# Sheet1.net
KiCad netlist of a schematic drawn in Altium Designer
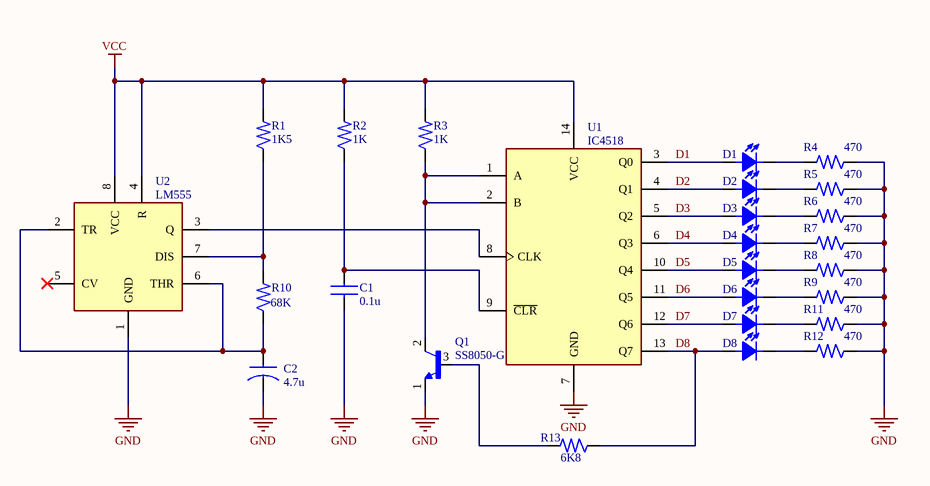
[diagram p0: Sheet1.SchDoc]

(export (version "E")
  (design (tool "Eeschema 10.0.6"))
  (components
    (comp (ref "C1") (value "0.1u") (footprint "CAP_8x11mm") (libsource (lib "Schlib1") (part "CAPACITOR")))
    (comp (ref "C2") (value "4.7u") (footprint "CAP_8x11mm") (libsource (lib "Schlib1") (part "CAPACITOR_1")))
    (comp (ref "D1") (value "LED") (footprint "LED-TH-2.54mm-RED") (libsource (lib "Schlib1") (part "LED")))
    (comp (ref "D2") (value "LED") (footprint "LED-TH-2.54mm-RED") (libsource (lib "Schlib1") (part "LED")))
    (comp (ref "D3") (value "LED") (footprint "LED-TH-2.54mm-RED") (libsource (lib "Schlib1") (part "LED")))
    (comp (ref "D4") (value "LED") (footprint "LED-TH-2.54mm-RED") (libsource (lib "Schlib1") (part "LED")))
    (comp (ref "D5") (value "LED") (footprint "LED-TH-2.54mm-RED") (libsource (lib "Schlib1") (part "LED")))
    (comp (ref "D6") (value "LED") (footprint "LED-TH-2.54mm-RED") (libsource (lib "Schlib1") (part "LED")))
    (comp (ref "D7") (value "LED") (footprint "LED-TH-2.54mm-RED") (libsource (lib "Schlib1") (part "LED")))
    (comp (ref "D8") (value "LED") (footprint "LED-TH-2.54mm-RED") (libsource (lib "Schlib1") (part "LED")))
    (comp (ref "Q1")
      (value "SS8050-G")
      (footprint "TO-92")
      (description "Bipolar (BJT) Transistor NPN 25 V 1.5 A 100MHz 300 mW Surface Mount SOT-23-3")
      (fields (field (name "DIGI-KEY_PART_NUMBER") "641-1790-2-ND") (field (name "MP") "SS8050G"))
      (libsource (lib "Schlib1") (part "SS8050-G"))
    )
    (comp (ref "R1") (value "1K5") (footprint "RES0805_SMD") (libsource (lib "Schlib1") (part "RESISTOR")))
    (comp (ref "R2") (value "1K") (footprint "RES0805_SMD") (libsource (lib "Schlib1") (part "RESISTOR")))
    (comp (ref "R3") (value "1K") (footprint "RES0805_SMD") (libsource (lib "Schlib1") (part "RESISTOR")))
    (comp (ref "R4") (value "470") (footprint "RES0805_SMD") (libsource (lib "Schlib1") (part "RESISTOR")))
    (comp (ref "R5") (value "470") (footprint "RES0805_SMD") (libsource (lib "Schlib1") (part "RESISTOR")))
    (comp (ref "R6") (value "470") (footprint "RES0805_SMD") (libsource (lib "Schlib1") (part "RESISTOR")))
    (comp (ref "R7") (value "470") (footprint "RES0805_SMD") (libsource (lib "Schlib1") (part "RESISTOR")))
    (comp (ref "R8") (value "470") (footprint "RES0805_SMD") (libsource (lib "Schlib1") (part "RESISTOR")))
    (comp (ref "R9") (value "470") (footprint "RES0805_SMD") (libsource (lib "Schlib1") (part "RESISTOR")))
    (comp (ref "R10") (value "68K") (footprint "RES0805_SMD") (libsource (lib "Schlib1") (part "RESISTOR")))
    (comp (ref "R11") (value "470") (footprint "RES0805_SMD") (libsource (lib "Schlib1") (part "RESISTOR")))
    (comp (ref "R12") (value "470") (footprint "RES0805_SMD") (libsource (lib "Schlib1") (part "RESISTOR")))
    (comp (ref "R13") (value "6K8") (footprint "RES0805_SMD") (libsource (lib "Schlib1") (part "RESISTOR")))
    (comp (ref "U1")
      (value "IC4518")
      (footprint "DIP794W45P254L1969H508Q14")
      (description "CMOS Dual BCD Up-Counter")
      (fields (field (name "MF") "Texas Instruments") (field (name "MP") "CD4518BE"))
      (libsource (lib "Schlib1") (part "IC4518"))
    )
    (comp (ref "U2")
      (value "LM555")
      (footprint "LM555")
      (description "Highly Stable 555 Timer")
      (fields (field (name "MF") "Texas Instruments") (field (name "MP") "LM555CN/NOPB"))
      (libsource (lib "Schlib1") (part "LM555CN/NOPB"))
    )
  )
  (nets
    (net (code "1") (name "/D1") (class "Default")
      (node (ref "D1") (pin "1") (pinfunction "A_1") (pintype "passive"))
      (node (ref "U1") (pin "3") (pinfunction "Q0_3") (pintype "passive"))
    )
    (net (code "2") (name "/D2") (class "Default")
      (node (ref "D2") (pin "1") (pinfunction "A_1") (pintype "passive"))
      (node (ref "U1") (pin "4") (pinfunction "Q1_4") (pintype "passive"))
    )
    (net (code "3") (name "/D3") (class "Default")
      (node (ref "D3") (pin "1") (pinfunction "A_1") (pintype "passive"))
      (node (ref "U1") (pin "5") (pinfunction "Q2_5") (pintype "passive"))
    )
    (net (code "4") (name "/D4") (class "Default")
      (node (ref "D4") (pin "1") (pinfunction "A_1") (pintype "passive"))
      (node (ref "U1") (pin "6") (pinfunction "Q3_6") (pintype "passive"))
    )
    (net (code "5") (name "/D5") (class "Default")
      (node (ref "D5") (pin "1") (pinfunction "A_1") (pintype "passive"))
      (node (ref "U1") (pin "10") (pinfunction "Q4_10") (pintype "passive"))
    )
    (net (code "6") (name "/D6") (class "Default")
      (node (ref "D6") (pin "1") (pinfunction "A_1") (pintype "passive"))
      (node (ref "U1") (pin "11") (pinfunction "Q5_11") (pintype "passive"))
    )
    (net (code "7") (name "/D7") (class "Default")
      (node (ref "D7") (pin "1") (pinfunction "A_1") (pintype "passive"))
      (node (ref "U1") (pin "12") (pinfunction "Q6_12") (pintype "passive"))
    )
    (net (code "8") (name "/D8") (class "Default")
      (node (ref "D8") (pin "1") (pinfunction "A_1") (pintype "passive"))
      (node (ref "R13") (pin "1") (pinfunction "1_1") (pintype "passive"))
      (node (ref "U1") (pin "13") (pinfunction "Q7_13") (pintype "passive"))
    )
    (net (code "9") (name "GND") (class "Default")
      (node (ref "C1") (pin "2") (pinfunction "2_2") (pintype "passive"))
      (node (ref "C2") (pin "2") (pinfunction "2_2") (pintype "passive"))
      (node (ref "Q1") (pin "1") (pinfunction "B_1") (pintype "passive"))
      (node (ref "R11") (pin "1") (pinfunction "1_1") (pintype "passive"))
      (node (ref "R12") (pin "1") (pinfunction "1_1") (pintype "passive"))
      (node (ref "R4") (pin "1") (pinfunction "1_1") (pintype "passive"))
      (node (ref "R5") (pin "1") (pinfunction "1_1") (pintype "passive"))
      (node (ref "R6") (pin "1") (pinfunction "1_1") (pintype "passive"))
      (node (ref "R7") (pin "1") (pinfunction "1_1") (pintype "passive"))
      (node (ref "R8") (pin "1") (pinfunction "1_1") (pintype "passive"))
      (node (ref "R9") (pin "1") (pinfunction "1_1") (pintype "passive"))
      (node (ref "U1") (pin "7") (pinfunction "GND_7") (pintype "passive"))
      (node (ref "U2") (pin "1") (pinfunction "GND_1") (pintype "power_in"))
    )
    (net (code "10") (name "Net-(D1-K)") (class "Default")
      (node (ref "D1") (pin "2") (pinfunction "K_2") (pintype "passive"))
      (node (ref "R4") (pin "2") (pinfunction "2_2") (pintype "passive"))
    )
    (net (code "11") (name "Net-(D2-K)") (class "Default")
      (node (ref "D2") (pin "2") (pinfunction "K_2") (pintype "passive"))
      (node (ref "R5") (pin "2") (pinfunction "2_2") (pintype "passive"))
    )
    (net (code "12") (name "Net-(D3-K)") (class "Default")
      (node (ref "D3") (pin "2") (pinfunction "K_2") (pintype "passive"))
      (node (ref "R6") (pin "2") (pinfunction "2_2") (pintype "passive"))
    )
    (net (code "13") (name "Net-(D4-K)") (class "Default")
      (node (ref "D4") (pin "2") (pinfunction "K_2") (pintype "passive"))
      (node (ref "R7") (pin "2") (pinfunction "2_2") (pintype "passive"))
    )
    (net (code "14") (name "Net-(D5-K)") (class "Default")
      (node (ref "D5") (pin "2") (pinfunction "K_2") (pintype "passive"))
      (node (ref "R8") (pin "2") (pinfunction "2_2") (pintype "passive"))
    )
    (net (code "15") (name "Net-(D6-K)") (class "Default")
      (node (ref "D6") (pin "2") (pinfunction "K_2") (pintype "passive"))
      (node (ref "R9") (pin "2") (pinfunction "2_2") (pintype "passive"))
    )
    (net (code "16") (name "Net-(D7-K)") (class "Default")
      (node (ref "D7") (pin "2") (pinfunction "K_2") (pintype "passive"))
      (node (ref "R11") (pin "2") (pinfunction "2_2") (pintype "passive"))
    )
    (net (code "17") (name "Net-(D8-K)") (class "Default")
      (node (ref "D8") (pin "2") (pinfunction "K_2") (pintype "passive"))
      (node (ref "R12") (pin "2") (pinfunction "2_2") (pintype "passive"))
    )
    (net (code "18") (name "Net-(Q1-C)") (class "Default")
      (node (ref "Q1") (pin "3") (pinfunction "C_3") (pintype "passive"))
      (node (ref "R13") (pin "2") (pinfunction "2_2") (pintype "passive"))
    )
    (net (code "19") (name "Net-(Q1-E)") (class "Default")
      (node (ref "Q1") (pin "2") (pinfunction "E_2") (pintype "passive"))
      (node (ref "R3") (pin "1") (pinfunction "1_1") (pintype "passive"))
      (node (ref "U1") (pin "1") (pinfunction "A_1") (pintype "passive"))
      (node (ref "U1") (pin "2") (pinfunction "B_2") (pintype "passive"))
    )
    (net (code "20") (name "Net-(U1-CLK)") (class "Default")
      (node (ref "U1") (pin "8") (pinfunction "CLK_8") (pintype "power_in"))
      (node (ref "U2") (pin "3") (pinfunction "Q_3") (pintype "passive"))
    )
    (net (code "21") (name "Net-(U1-~{CLR})") (class "Default")
      (node (ref "C1") (pin "1") (pinfunction "1_1") (pintype "passive"))
      (node (ref "R2") (pin "1") (pinfunction "1_1") (pintype "passive"))
      (node (ref "U1") (pin "9") (pinfunction "~{CLR}_9") (pintype "passive"))
    )
    (net (code "22") (name "Net-(U2-DIS)") (class "Default")
      (node (ref "R1") (pin "1") (pinfunction "1_1") (pintype "passive"))
      (node (ref "R10") (pin "2") (pinfunction "2_2") (pintype "passive"))
      (node (ref "U2") (pin "7") (pinfunction "DIS_7") (pintype "passive"))
    )
    (net (code "23") (name "Net-(U2-THR)") (class "Default")
      (node (ref "C2") (pin "1") (pinfunction "1_1") (pintype "passive"))
      (node (ref "R10") (pin "1") (pinfunction "1_1") (pintype "passive"))
      (node (ref "U2") (pin "2") (pinfunction "TR_2") (pintype "passive"))
      (node (ref "U2") (pin "6") (pinfunction "THR_6") (pintype "passive"))
    )
    (net (code "24") (name "VCC") (class "Default")
      (node (ref "R1") (pin "2") (pinfunction "2_2") (pintype "passive"))
      (node (ref "R2") (pin "2") (pinfunction "2_2") (pintype "passive"))
      (node (ref "R3") (pin "2") (pinfunction "2_2") (pintype "passive"))
      (node (ref "U1") (pin "14") (pinfunction "VCC_14") (pintype "passive"))
      (node (ref "U2") (pin "4") (pinfunction "R_4") (pintype "passive"))
      (node (ref "U2") (pin "8") (pinfunction "VCC_8") (pintype "power_in"))
    )
    (net (code "25") (name "unconnected-(U2-CV-Pad5)") (class "Default")
      (node (ref "U2") (pin "5") (pinfunction "CV_5") (pintype "passive+no_connect"))
    )
  )
)
